# SoftRobotController.net
KiCad netlist of a schematic drawn in Altium Designer
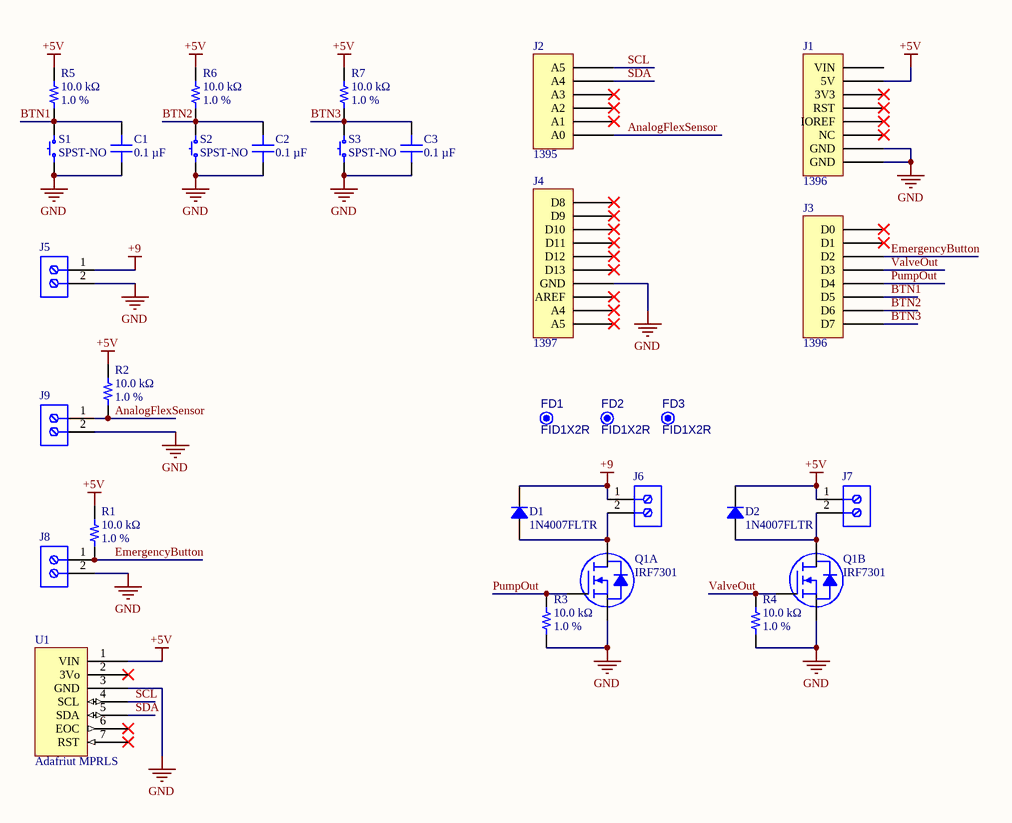
[diagram p0: SoftRobotController.SchDoc]

(export (version "E")
  (design (tool "Eeschema 10.0.6"))
  (components
    (comp (ref "C1")
      (value "0.1 µF")
      (footprint "CAP 0603_1608")
      (description "CAP CER 0.1UF 16V X7R 0603")
      (fields (field (name "PART NUMBER") "CS0603KRX7R7BB104") (field (name "MANUFACTURER") "Yageo"))
      (libsource (lib "Celestial Altium Library - altium_library") (part "Capacitor"))
    )
    (comp (ref "C2")
      (value "0.1 µF")
      (footprint "CAP 0603_1608")
      (description "CAP CER 0.1UF 16V X7R 0603")
      (fields (field (name "PART NUMBER") "CS0603KRX7R7BB104") (field (name "MANUFACTURER") "Yageo"))
      (libsource (lib "Celestial Altium Library - altium_library") (part "Capacitor"))
    )
    (comp (ref "C3")
      (value "0.1 µF")
      (footprint "CAP 0603_1608")
      (description "CAP CER 0.1UF 16V X7R 0603")
      (fields (field (name "PART NUMBER") "CS0603KRX7R7BB104") (field (name "MANUFACTURER") "Yageo"))
      (libsource (lib "Celestial Altium Library - altium_library") (part "Capacitor"))
    )
    (comp (ref "D1")
      (value "1N4007FLTR")
      (footprint "SOD123F")
      (description "STANDARD RECTIFIER 1000V SOD-123")
      (fields (field (name "MANUFACTURER") "SMC Diode Solutions"))
      (libsource (lib "Celestial Altium Library - altium_library") (part "Diode"))
    )
    (comp (ref "D2")
      (value "1N4007FLTR")
      (footprint "SOD123F")
      (description "STANDARD RECTIFIER 1000V SOD-123")
      (fields (field (name "MANUFACTURER") "SMC Diode Solutions"))
      (libsource (lib "Celestial Altium Library - altium_library") (part "Diode"))
    )
    (comp (ref "FD1")
      (value "FID1X2R")
      (footprint "FID1X2R")
      (description "Fiducial - Round 1x2mm")
      (libsource (lib "Rowan University") (part "CMP-00134-2"))
    )
    (comp (ref "FD2")
      (value "FID1X2R")
      (footprint "FID1X2R")
      (description "Fiducial - Round 1x2mm")
      (libsource (lib "Rowan University") (part "CMP-00134-2"))
    )
    (comp (ref "FD3")
      (value "FID1X2R")
      (footprint "FID1X2R")
      (description "Fiducial - Round 1x2mm")
      (libsource (lib "Rowan University") (part "CMP-00134-2"))
    )
    (comp (ref "J1")
      (value "1396")
      (footprint "PCB - CONNECTOR - HEADER - MALE 1X8")
      (description "Connector Header Through Hole 8 position 0.100&quot; (2.54mm)")
      (fields
        (field (name "MANUFACTURER") "Sullins Connector Solutions")
        (field (name "MANUFACTURER PART NUMBER") "PRPC008SAAN-RC")
      )
      (libsource (lib "") (part "SCH - CONNECTORS - 8 PIN_1"))
    )
    (comp (ref "J2")
      (value "1395")
      (footprint "PCB - CONNECTOR - HEADER - MALE 1X6")
      (description "Connector Header Through Hole 6 position 0.100&quot; (2.54mm)")
      (fields
        (field (name "MANUFACTURER") "Sullins Connector Solutions")
        (field (name "MANUFACTURER PART NUMBER") "PRPC006SAAN-RC")
      )
      (libsource (lib "Rowan University") (part "SCH - CONNECTORS - 6 PIN"))
    )
    (comp (ref "J3")
      (value "1396")
      (footprint "PCB - CONNECTOR - HEADER - MALE 1X8")
      (description "Connector Header Through Hole 8 position 0.100&quot; (2.54mm)")
      (fields
        (field (name "MANUFACTURER") "Sullins Connector Solutions")
        (field (name "MANUFACTURER PART NUMBER") "PRPC008SAAN-RC")
      )
      (libsource (lib "Rowan University") (part "SCH - CONNECTORS - 8 PIN"))
    )
    (comp (ref "J4")
      (value "1397")
      (footprint "PCB - CONNECTOR - HEADER - MALE 1X10")
      (description "Connector Header Through Hole 10 position 0.100&quot; (2.54mm)")
      (fields
        (field (name "MANUFACTURER") "Sullins Connector Solutions")
        (field (name "MANUFACTURER PART NUMBER") "PRPC010SAAN-RC")
      )
      (libsource (lib "Rowan University") (part "SCH - CONNECTORS - 10 PIN"))
    )
    (comp (ref "J5")
      (value "691103110002")
      (footprint "691103110002")
      (description "Series 1031 - 3.50 mm Horizontal Entry Modular with Pressure Clamp WR-TBL, 2 pin")
      (fields (field (name "MANUFACTURER") "Wurth Elektronik") (field (name "PUBLISHER") "WurthElektronik"))
      (libsource (lib "Altium Content Vault") (part "WE-CN-1P-F-TB2"))
    )
    (comp (ref "J6")
      (value "691103110002")
      (footprint "691103110002")
      (description "Series 1031 - 3.50 mm Horizontal Entry Modular with Pressure Clamp WR-TBL, 2 pin")
      (fields (field (name "MANUFACTURER") "Wurth Elektronik") (field (name "PUBLISHER") "WurthElektronik"))
      (libsource (lib "Altium Content Vault") (part "WE-CN-1P-F-TB2"))
    )
    (comp (ref "J7")
      (value "691103110002")
      (footprint "691103110002")
      (description "Series 1031 - 3.50 mm Horizontal Entry Modular with Pressure Clamp WR-TBL, 2 pin")
      (fields (field (name "MANUFACTURER") "Wurth Elektronik") (field (name "PUBLISHER") "WurthElektronik"))
      (libsource (lib "Altium Content Vault") (part "WE-CN-1P-F-TB2"))
    )
    (comp (ref "J8")
      (value "691103110002")
      (footprint "691103110002")
      (description "Series 1031 - 3.50 mm Horizontal Entry Modular with Pressure Clamp WR-TBL, 2 pin")
      (fields (field (name "MANUFACTURER") "Wurth Elektronik") (field (name "PUBLISHER") "WurthElektronik"))
      (libsource (lib "Altium Content Vault") (part "WE-CN-1P-F-TB2"))
    )
    (comp (ref "J9")
      (value "691103110002")
      (footprint "691103110002")
      (description "Series 1031 - 3.50 mm Horizontal Entry Modular with Pressure Clamp WR-TBL, 2 pin")
      (fields (field (name "MANUFACTURER") "Wurth Elektronik") (field (name "PUBLISHER") "WurthElektronik"))
      (libsource (lib "Altium Content Vault") (part "WE-CN-1P-F-TB2"))
    )
    (comp (ref "Q1")
      (value "IRF7301")
      (footprint "IRF7301")
      (libsource (lib "SoftRobotics") (part "IRF7301"))
    )
    (comp (ref "R1")
      (value "10.0 kΩ")
      (footprint "PCB - RESISTOR - CHIP - RES 0603_1608")
      (description "10 kOhms ±1% 0.1W, 1/10W Chip Resistor 0603 (1608 Metric) Moisture Resistant Thick Film")
      (fields
        (field (name "ROWAN PART NUMBER") "1416")
        (field (name "TOLERANCE") "1.0 %")
        (field (name "MANUFACTURER") "Yageo")
      )
      (libsource (lib "RowanAltiumLibrary") (part "SCH - PASSIVES - RESISTOR"))
    )
    (comp (ref "R2")
      (value "10.0 kΩ")
      (footprint "PCB - RESISTOR - CHIP - RES 0603_1608")
      (description "10 kOhms ±1% 0.1W, 1/10W Chip Resistor 0603 (1608 Metric) Moisture Resistant Thick Film")
      (fields
        (field (name "ROWAN PART NUMBER") "1416")
        (field (name "TOLERANCE") "1.0 %")
        (field (name "MANUFACTURER") "Yageo")
      )
      (libsource (lib "RowanAltiumLibrary") (part "SCH - PASSIVES - RESISTOR"))
    )
    (comp (ref "R3")
      (value "10.0 kΩ")
      (footprint "PCB - RESISTOR - CHIP - RES 0603_1608")
      (description "10 kOhms ±1% 0.1W, 1/10W Chip Resistor 0603 (1608 Metric) Moisture Resistant Thick Film")
      (fields
        (field (name "ROWAN PART NUMBER") "1416")
        (field (name "TOLERANCE") "1.0 %")
        (field (name "MANUFACTURER") "Yageo")
      )
      (libsource (lib "RowanAltiumLibrary") (part "SCH - PASSIVES - RESISTOR"))
    )
    (comp (ref "R4")
      (value "10.0 kΩ")
      (footprint "PCB - RESISTOR - CHIP - RES 0603_1608")
      (description "10 kOhms ±1% 0.1W, 1/10W Chip Resistor 0603 (1608 Metric) Moisture Resistant Thick Film")
      (fields
        (field (name "ROWAN PART NUMBER") "1416")
        (field (name "TOLERANCE") "1.0 %")
        (field (name "MANUFACTURER") "Yageo")
      )
      (libsource (lib "RowanAltiumLibrary") (part "SCH - PASSIVES - RESISTOR"))
    )
    (comp (ref "R5")
      (value "10.0 kΩ")
      (footprint "PCB - RESISTOR - CHIP - RES 0603_1608")
      (description "10 kOhms ±1% 0.1W, 1/10W Chip Resistor 0603 (1608 Metric) Moisture Resistant Thick Film")
      (fields
        (field (name "ROWAN PART NUMBER") "1416")
        (field (name "TOLERANCE") "1.0 %")
        (field (name "MANUFACTURER") "Yageo")
      )
      (libsource (lib "RowanAltiumLibrary") (part "SCH - PASSIVES - RESISTOR"))
    )
    (comp (ref "R6")
      (value "10.0 kΩ")
      (footprint "PCB - RESISTOR - CHIP - RES 0603_1608")
      (description "10 kOhms ±1% 0.1W, 1/10W Chip Resistor 0603 (1608 Metric) Moisture Resistant Thick Film")
      (fields
        (field (name "ROWAN PART NUMBER") "1416")
        (field (name "TOLERANCE") "1.0 %")
        (field (name "MANUFACTURER") "Yageo")
      )
      (libsource (lib "RowanAltiumLibrary") (part "SCH - PASSIVES - RESISTOR"))
    )
    (comp (ref "R7")
      (value "10.0 kΩ")
      (footprint "PCB - RESISTOR - CHIP - RES 0603_1608")
      (description "10 kOhms ±1% 0.1W, 1/10W Chip Resistor 0603 (1608 Metric) Moisture Resistant Thick Film")
      (fields
        (field (name "ROWAN PART NUMBER") "1416")
        (field (name "TOLERANCE") "1.0 %")
        (field (name "MANUFACTURER") "Yageo")
      )
      (libsource (lib "RowanAltiumLibrary") (part "SCH - PASSIVES - RESISTOR"))
    )
    (comp (ref "S1")
      (value "SPST-NO")
      (footprint "PTS641SK31SMTR2LFS")
      (libsource (lib "SoftRobotics") (part "PTS641SK31SMTR2LFS"))
    )
    (comp (ref "S2")
      (value "SPST-NO")
      (footprint "PTS641SK31SMTR2LFS")
      (libsource (lib "SoftRobotics") (part "PTS641SK31SMTR2LFS"))
    )
    (comp (ref "S3")
      (value "SPST-NO")
      (footprint "PTS641SK31SMTR2LFS")
      (libsource (lib "SoftRobotics") (part "PTS641SK31SMTR2LFS"))
    )
    (comp (ref "U1")
      (value "Adafriut MPRLS")
      (footprint "ADAFRUITMPRLS")
      (libsource (lib "SoftRobotics") (part "AdafruitMPRLS"))
    )
  )
  (nets
    (net (code "1") (name "+5V") (class "Default")
      (node (ref "D2") (pin "2") (pinfunction "2_2") (pintype "passive"))
      (node (ref "J1") (pin "5") (pinfunction "5V_5") (pintype "passive"))
      (node (ref "J7") (pin "1") (pinfunction "1_1") (pintype "passive"))
      (node (ref "R1") (pin "2") (pinfunction "2_2") (pintype "passive"))
      (node (ref "R2") (pin "2") (pinfunction "2_2") (pintype "passive"))
      (node (ref "R5") (pin "2") (pinfunction "2_2") (pintype "passive"))
      (node (ref "R6") (pin "2") (pinfunction "2_2") (pintype "passive"))
      (node (ref "R7") (pin "2") (pinfunction "2_2") (pintype "passive"))
      (node (ref "U1") (pin "1") (pinfunction "VIN_1") (pintype "power_in"))
    )
    (net (code "2") (name "+9") (class "Default")
      (node (ref "D1") (pin "2") (pinfunction "2_2") (pintype "passive"))
      (node (ref "J5") (pin "1") (pinfunction "1_1") (pintype "passive"))
      (node (ref "J6") (pin "1") (pinfunction "1_1") (pintype "passive"))
    )
    (net (code "3") (name "/AnalogFlexSensor") (class "Default")
      (node (ref "J2") (pin "6") (pinfunction "A0_6") (pintype "passive"))
      (node (ref "J9") (pin "1") (pinfunction "1_1") (pintype "passive"))
      (node (ref "R2") (pin "1") (pinfunction "1_1") (pintype "passive"))
    )
    (net (code "4") (name "/BTN1") (class "Default")
      (node (ref "C1") (pin "2") (pinfunction "2_2") (pintype "passive"))
      (node (ref "J3") (pin "6") (pinfunction "D5_6") (pintype "passive"))
      (node (ref "R5") (pin "1") (pinfunction "1_1") (pintype "passive"))
      (node (ref "S1") (pin "3") (pinfunction "3_3") (pintype "passive"))
      (node (ref "S1") (pin "4") (pinfunction "4_4") (pintype "passive"))
    )
    (net (code "5") (name "/BTN2") (class "Default")
      (node (ref "C2") (pin "2") (pinfunction "2_2") (pintype "passive"))
      (node (ref "J3") (pin "7") (pinfunction "D6_7") (pintype "passive"))
      (node (ref "R6") (pin "1") (pinfunction "1_1") (pintype "passive"))
      (node (ref "S2") (pin "3") (pinfunction "3_3") (pintype "passive"))
      (node (ref "S2") (pin "4") (pinfunction "4_4") (pintype "passive"))
    )
    (net (code "6") (name "/BTN3") (class "Default")
      (node (ref "C3") (pin "2") (pinfunction "2_2") (pintype "passive"))
      (node (ref "J3") (pin "8") (pinfunction "D7_8") (pintype "passive"))
      (node (ref "R7") (pin "1") (pinfunction "1_1") (pintype "passive"))
      (node (ref "S3") (pin "3") (pinfunction "3_3") (pintype "passive"))
      (node (ref "S3") (pin "4") (pinfunction "4_4") (pintype "passive"))
    )
    (net (code "7") (name "/EmergencyButton") (class "Default")
      (node (ref "J3") (pin "3") (pinfunction "D2_3") (pintype "passive"))
      (node (ref "J8") (pin "1") (pinfunction "1_1") (pintype "passive"))
      (node (ref "R1") (pin "1") (pinfunction "1_1") (pintype "passive"))
    )
    (net (code "8") (name "/PumpOut") (class "Default")
      (node (ref "J3") (pin "5") (pinfunction "D4_5") (pintype "passive"))
      (node (ref "Q1") (pin "2") (pinfunction "G1_2") (pintype "passive"))
      (node (ref "R3") (pin "2") (pinfunction "2_2") (pintype "passive"))
    )
    (net (code "9") (name "/SCL") (class "Default")
      (node (ref "J2") (pin "1") (pinfunction "A5_1") (pintype "passive"))
      (node (ref "U1") (pin "4") (pinfunction "SCL_4") (pintype "bidirectional"))
    )
    (net (code "10") (name "/SDA") (class "Default")
      (node (ref "J2") (pin "2") (pinfunction "A4_2") (pintype "passive"))
      (node (ref "U1") (pin "5") (pinfunction "SDA_5") (pintype "bidirectional"))
    )
    (net (code "11") (name "/ValveOut") (class "Default")
      (node (ref "J3") (pin "4") (pinfunction "D3_4") (pintype "passive"))
      (node (ref "Q1") (pin "4") (pinfunction "G2_4") (pintype "passive"))
      (node (ref "R4") (pin "2") (pinfunction "2_2") (pintype "passive"))
    )
    (net (code "12") (name "GND") (class "Default")
      (node (ref "C1") (pin "1") (pinfunction "1_1") (pintype "passive"))
      (node (ref "C2") (pin "1") (pinfunction "1_1") (pintype "passive"))
      (node (ref "C3") (pin "1") (pinfunction "1_1") (pintype "passive"))
      (node (ref "J1") (pin "6") (pinfunction "GND_6") (pintype "passive"))
      (node (ref "J1") (pin "7") (pinfunction "GND_7") (pintype "passive"))
      (node (ref "J4") (pin "7") (pinfunction "GND_7") (pintype "passive"))
      (node (ref "J5") (pin "2") (pinfunction "2_2") (pintype "passive"))
      (node (ref "J8") (pin "2") (pinfunction "2_2") (pintype "passive"))
      (node (ref "J9") (pin "2") (pinfunction "2_2") (pintype "passive"))
      (node (ref "Q1") (pin "1") (pinfunction "S1_1") (pintype "passive"))
      (node (ref "Q1") (pin "3") (pinfunction "S2_3") (pintype "passive"))
      (node (ref "R3") (pin "1") (pinfunction "1_1") (pintype "passive"))
      (node (ref "R4") (pin "1") (pinfunction "1_1") (pintype "passive"))
      (node (ref "S1") (pin "1") (pinfunction "1_1") (pintype "passive"))
      (node (ref "S1") (pin "2") (pinfunction "2_2") (pintype "passive"))
      (node (ref "S2") (pin "1") (pinfunction "1_1") (pintype "passive"))
      (node (ref "S2") (pin "2") (pinfunction "2_2") (pintype "passive"))
      (node (ref "S3") (pin "1") (pinfunction "1_1") (pintype "passive"))
      (node (ref "S3") (pin "2") (pinfunction "2_2") (pintype "passive"))
      (node (ref "U1") (pin "3") (pinfunction "GND_3") (pintype "power_in"))
    )
    (net (code "13") (name "Net-(D1-Pad1)") (class "Default")
      (node (ref "D1") (pin "1") (pinfunction "1_1") (pintype "passive"))
      (node (ref "J6") (pin "2") (pinfunction "2_2") (pintype "passive"))
      (node (ref "Q1") (pin "7") (pinfunction "D1_7") (pintype "passive"))
      (node (ref "Q1") (pin "8") (pinfunction "D1_8") (pintype "passive"))
    )
    (net (code "14") (name "Net-(Q1B-D2)") (class "Default")
      (node (ref "D2") (pin "1") (pinfunction "1_1") (pintype "passive"))
      (node (ref "J7") (pin "2") (pinfunction "2_2") (pintype "passive"))
      (node (ref "Q1") (pin "5") (pinfunction "D2_5") (pintype "passive"))
      (node (ref "Q1") (pin "6") (pinfunction "D3_6") (pintype "passive"))
    )
    (net (code "15") (name "unconnected-(J1-3V3-Pad4)") (class "Default")
      (node (ref "J1") (pin "4") (pinfunction "3V3_4") (pintype "passive+no_connect"))
    )
    (net (code "16") (name "unconnected-(J1-IOREF-Pad2)") (class "Default")
      (node (ref "J1") (pin "2") (pinfunction "IOREF_2") (pintype "passive+no_connect"))
    )
    (net (code "17") (name "unconnected-(J1-NC-Pad1)") (class "Default")
      (node (ref "J1") (pin "1") (pinfunction "NC_1") (pintype "passive+no_connect"))
    )
    (net (code "18") (name "unconnected-(J1-RST-Pad3)") (class "Default")
      (node (ref "J1") (pin "3") (pinfunction "RST_3") (pintype "passive+no_connect"))
    )
    (net (code "19") (name "unconnected-(J1-VIN-Pad8)") (class "Default")
      (node (ref "J1") (pin "8") (pinfunction "VIN_8") (pintype "passive"))
    )
    (net (code "20") (name "unconnected-(J2-A1-Pad5)") (class "Default")
      (node (ref "J2") (pin "5") (pinfunction "A1_5") (pintype "passive+no_connect"))
    )
    (net (code "21") (name "unconnected-(J2-A2-Pad4)") (class "Default")
      (node (ref "J2") (pin "4") (pinfunction "A2_4") (pintype "passive+no_connect"))
    )
    (net (code "22") (name "unconnected-(J2-A3-Pad3)") (class "Default")
      (node (ref "J2") (pin "3") (pinfunction "A3_3") (pintype "passive+no_connect"))
    )
    (net (code "23") (name "unconnected-(J3-D0-Pad1)") (class "Default")
      (node (ref "J3") (pin "1") (pinfunction "D0_1") (pintype "passive+no_connect"))
    )
    (net (code "24") (name "unconnected-(J3-D1-Pad2)") (class "Default")
      (node (ref "J3") (pin "2") (pinfunction "D1_2") (pintype "passive+no_connect"))
    )
    (net (code "25") (name "unconnected-(J4-A4-Pad9)") (class "Default")
      (node (ref "J4") (pin "9") (pinfunction "A4_9") (pintype "passive+no_connect"))
    )
    (net (code "26") (name "unconnected-(J4-A5-Pad10)") (class "Default")
      (node (ref "J4") (pin "10") (pinfunction "A5_10") (pintype "passive+no_connect"))
    )
    (net (code "27") (name "unconnected-(J4-AREF-Pad8)") (class "Default")
      (node (ref "J4") (pin "8") (pinfunction "AREF_8") (pintype "passive+no_connect"))
    )
    (net (code "28") (name "unconnected-(J4-D8-Pad1)") (class "Default")
      (node (ref "J4") (pin "1") (pinfunction "D8_1") (pintype "passive+no_connect"))
    )
    (net (code "29") (name "unconnected-(J4-D9-Pad2)") (class "Default")
      (node (ref "J4") (pin "2") (pinfunction "D9_2") (pintype "passive+no_connect"))
    )
    (net (code "30") (name "unconnected-(J4-D10-Pad3)") (class "Default")
      (node (ref "J4") (pin "3") (pinfunction "D10_3") (pintype "passive+no_connect"))
    )
    (net (code "31") (name "unconnected-(J4-D11-Pad4)") (class "Default")
      (node (ref "J4") (pin "4") (pinfunction "D11_4") (pintype "passive+no_connect"))
    )
    (net (code "32") (name "unconnected-(J4-D12-Pad5)") (class "Default")
      (node (ref "J4") (pin "5") (pinfunction "D12_5") (pintype "passive+no_connect"))
    )
    (net (code "33") (name "unconnected-(J4-D13-Pad6)") (class "Default")
      (node (ref "J4") (pin "6") (pinfunction "D13_6") (pintype "passive+no_connect"))
    )
    (net (code "34") (name "unconnected-(U1-3Vo-Pad2)") (class "Default")
      (node (ref "U1") (pin "2") (pinfunction "3Vo_2") (pintype "power_in+no_connect"))
    )
    (net (code "35") (name "unconnected-(U1-EOC-Pad6)") (class "Default")
      (node (ref "U1") (pin "6") (pinfunction "EOC_6") (pintype "output+no_connect"))
    )
    (net (code "36") (name "unconnected-(U1-RST-Pad7)") (class "Default")
      (node (ref "U1") (pin "7") (pinfunction "RST_7") (pintype "input+no_connect"))
    )
  )
)
